# CAN_Breakout.net
KiCad netlist of a schematic drawn in Altium Designer
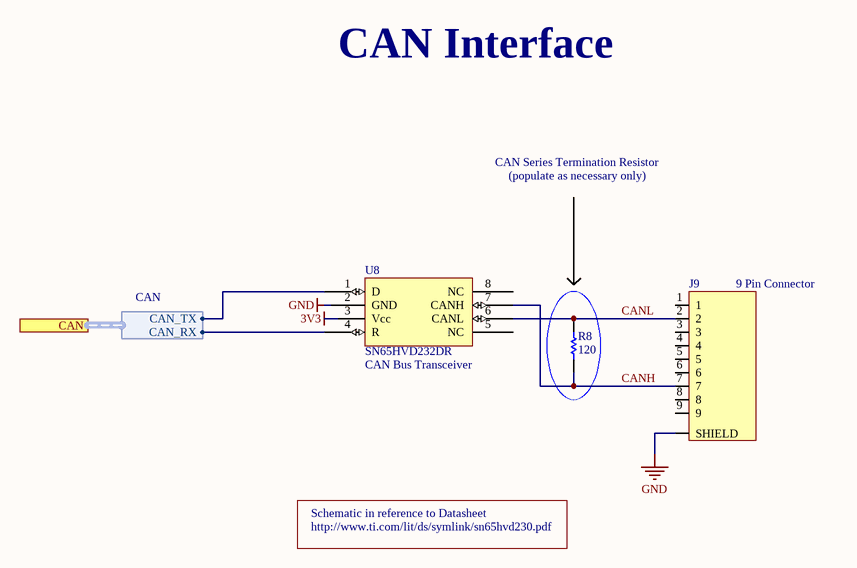
[diagram p0: CAN_Breakout.SchDoc]

(export (version "E")
  (design (tool "Eeschema 10.0.6"))
  (components
    (comp (ref "J9")
      (value "9 Pin Connector")
      (footprint "LaunchyRIOFootprints:9-Pos D-Sub")
      (description "9-Position Connector")
      (libsource (lib "LaunchyRIOComponents") (part "9-Position Connector"))
    )
    (comp (ref "R8")
      (value "120")
      (footprint "0402")
      (description "Resistor")
      (fields (field (name "Comment") "Res1"))
      (libsource (lib "Miscellaneous Devices") (part "Res1"))
    )
    (comp (ref "U8")
      (value "CAN Bus Transceiver")
      (footprint "8SOIC-CAN-TRANSCEIVER")
      (fields
        (field (name "MANUFACTURER") "Texas Instruments")
        (field (name "MANUFACTURER PART NUMBER") "SN65HVD232DR")
        (field (name "DIGIKEY PART NUMBER") "296-26344-1-ND")
      )
      (libsource (lib "LaunchyRIOComponents") (part "SN65HVD232DR"))
    )
  )
  (nets
    (net (code "2") (name "/CANH") (class "Default")
      (node (ref "J9") (pin "7") (pinfunction "7_7") (pintype "bidirectional"))
      (node (ref "R8") (pin "1") (pinfunction "1_1") (pintype "passive"))
      (node (ref "U8") (pin "7") (pinfunction "CANH_7") (pintype "bidirectional"))
    )
    (net (code "3") (name "/CANL") (class "Default")
      (node (ref "J9") (pin "2") (pinfunction "2_2") (pintype "bidirectional"))
      (node (ref "R8") (pin "2") (pinfunction "2_2") (pintype "passive"))
      (node (ref "U8") (pin "6") (pinfunction "CANL_6") (pintype "bidirectional"))
    )
    (net (code "4") (name "/CAN_RX") (class "Default")
      (node (ref "U8") (pin "4") (pinfunction "R_4") (pintype "bidirectional"))
    )
    (net (code "5") (name "/CAN_TX") (class "Default")
      (node (ref "U8") (pin "1") (pinfunction "D_1") (pintype "bidirectional"))
    )
    (net (code "7") (name "3V3") (class "Default")
      (node (ref "U8") (pin "3") (pinfunction "Vcc_3") (pintype "power_in"))
    )
    (net (code "8") (name "GND") (class "Default")
      (node (ref "J9") (pin "SHIELD") (pinfunction "SHIELD_SHIELD") (pintype "passive"))
      (node (ref "U8") (pin "2") (pinfunction "GND_2") (pintype "power_in"))
    )
    (net (code "9") (name "unconnected-(J9-Pad1)") (class "Default")
      (node (ref "J9") (pin "1") (pinfunction "1_1") (pintype "bidirectional"))
    )
    (net (code "10") (name "unconnected-(J9-Pad3)") (class "Default")
      (node (ref "J9") (pin "3") (pinfunction "3_3") (pintype "bidirectional"))
    )
    (net (code "11") (name "unconnected-(J9-Pad4)") (class "Default")
      (node (ref "J9") (pin "4") (pinfunction "4_4") (pintype "bidirectional"))
    )
    (net (code "12") (name "unconnected-(J9-Pad5)") (class "Default")
      (node (ref "J9") (pin "5") (pinfunction "5_5") (pintype "bidirectional"))
    )
    (net (code "13") (name "unconnected-(J9-Pad6)") (class "Default")
      (node (ref "J9") (pin "6") (pinfunction "6_6") (pintype "bidirectional"))
    )
    (net (code "14") (name "unconnected-(J9-Pad8)") (class "Default")
      (node (ref "J9") (pin "8") (pinfunction "8_8") (pintype "bidirectional"))
    )
    (net (code "15") (name "unconnected-(J9-Pad9)") (class "Default")
      (node (ref "J9") (pin "9") (pinfunction "9_9") (pintype "bidirectional"))
    )
    (net (code "16") (name "unconnected-(U8-NC-Pad5)") (class "Default")
      (node (ref "U8") (pin "5") (pinfunction "NC_5") (pintype "passive"))
    )
    (net (code "17") (name "unconnected-(U8-NC-Pad8)") (class "Default")
      (node (ref "U8") (pin "8") (pinfunction "NC_8") (pintype "passive"))
    )
  )
)
